# ProPrj_40HZ-AMSAD_2024-06-22.net
KiCad netlist of a schematic drawn in EasyEDA Pro
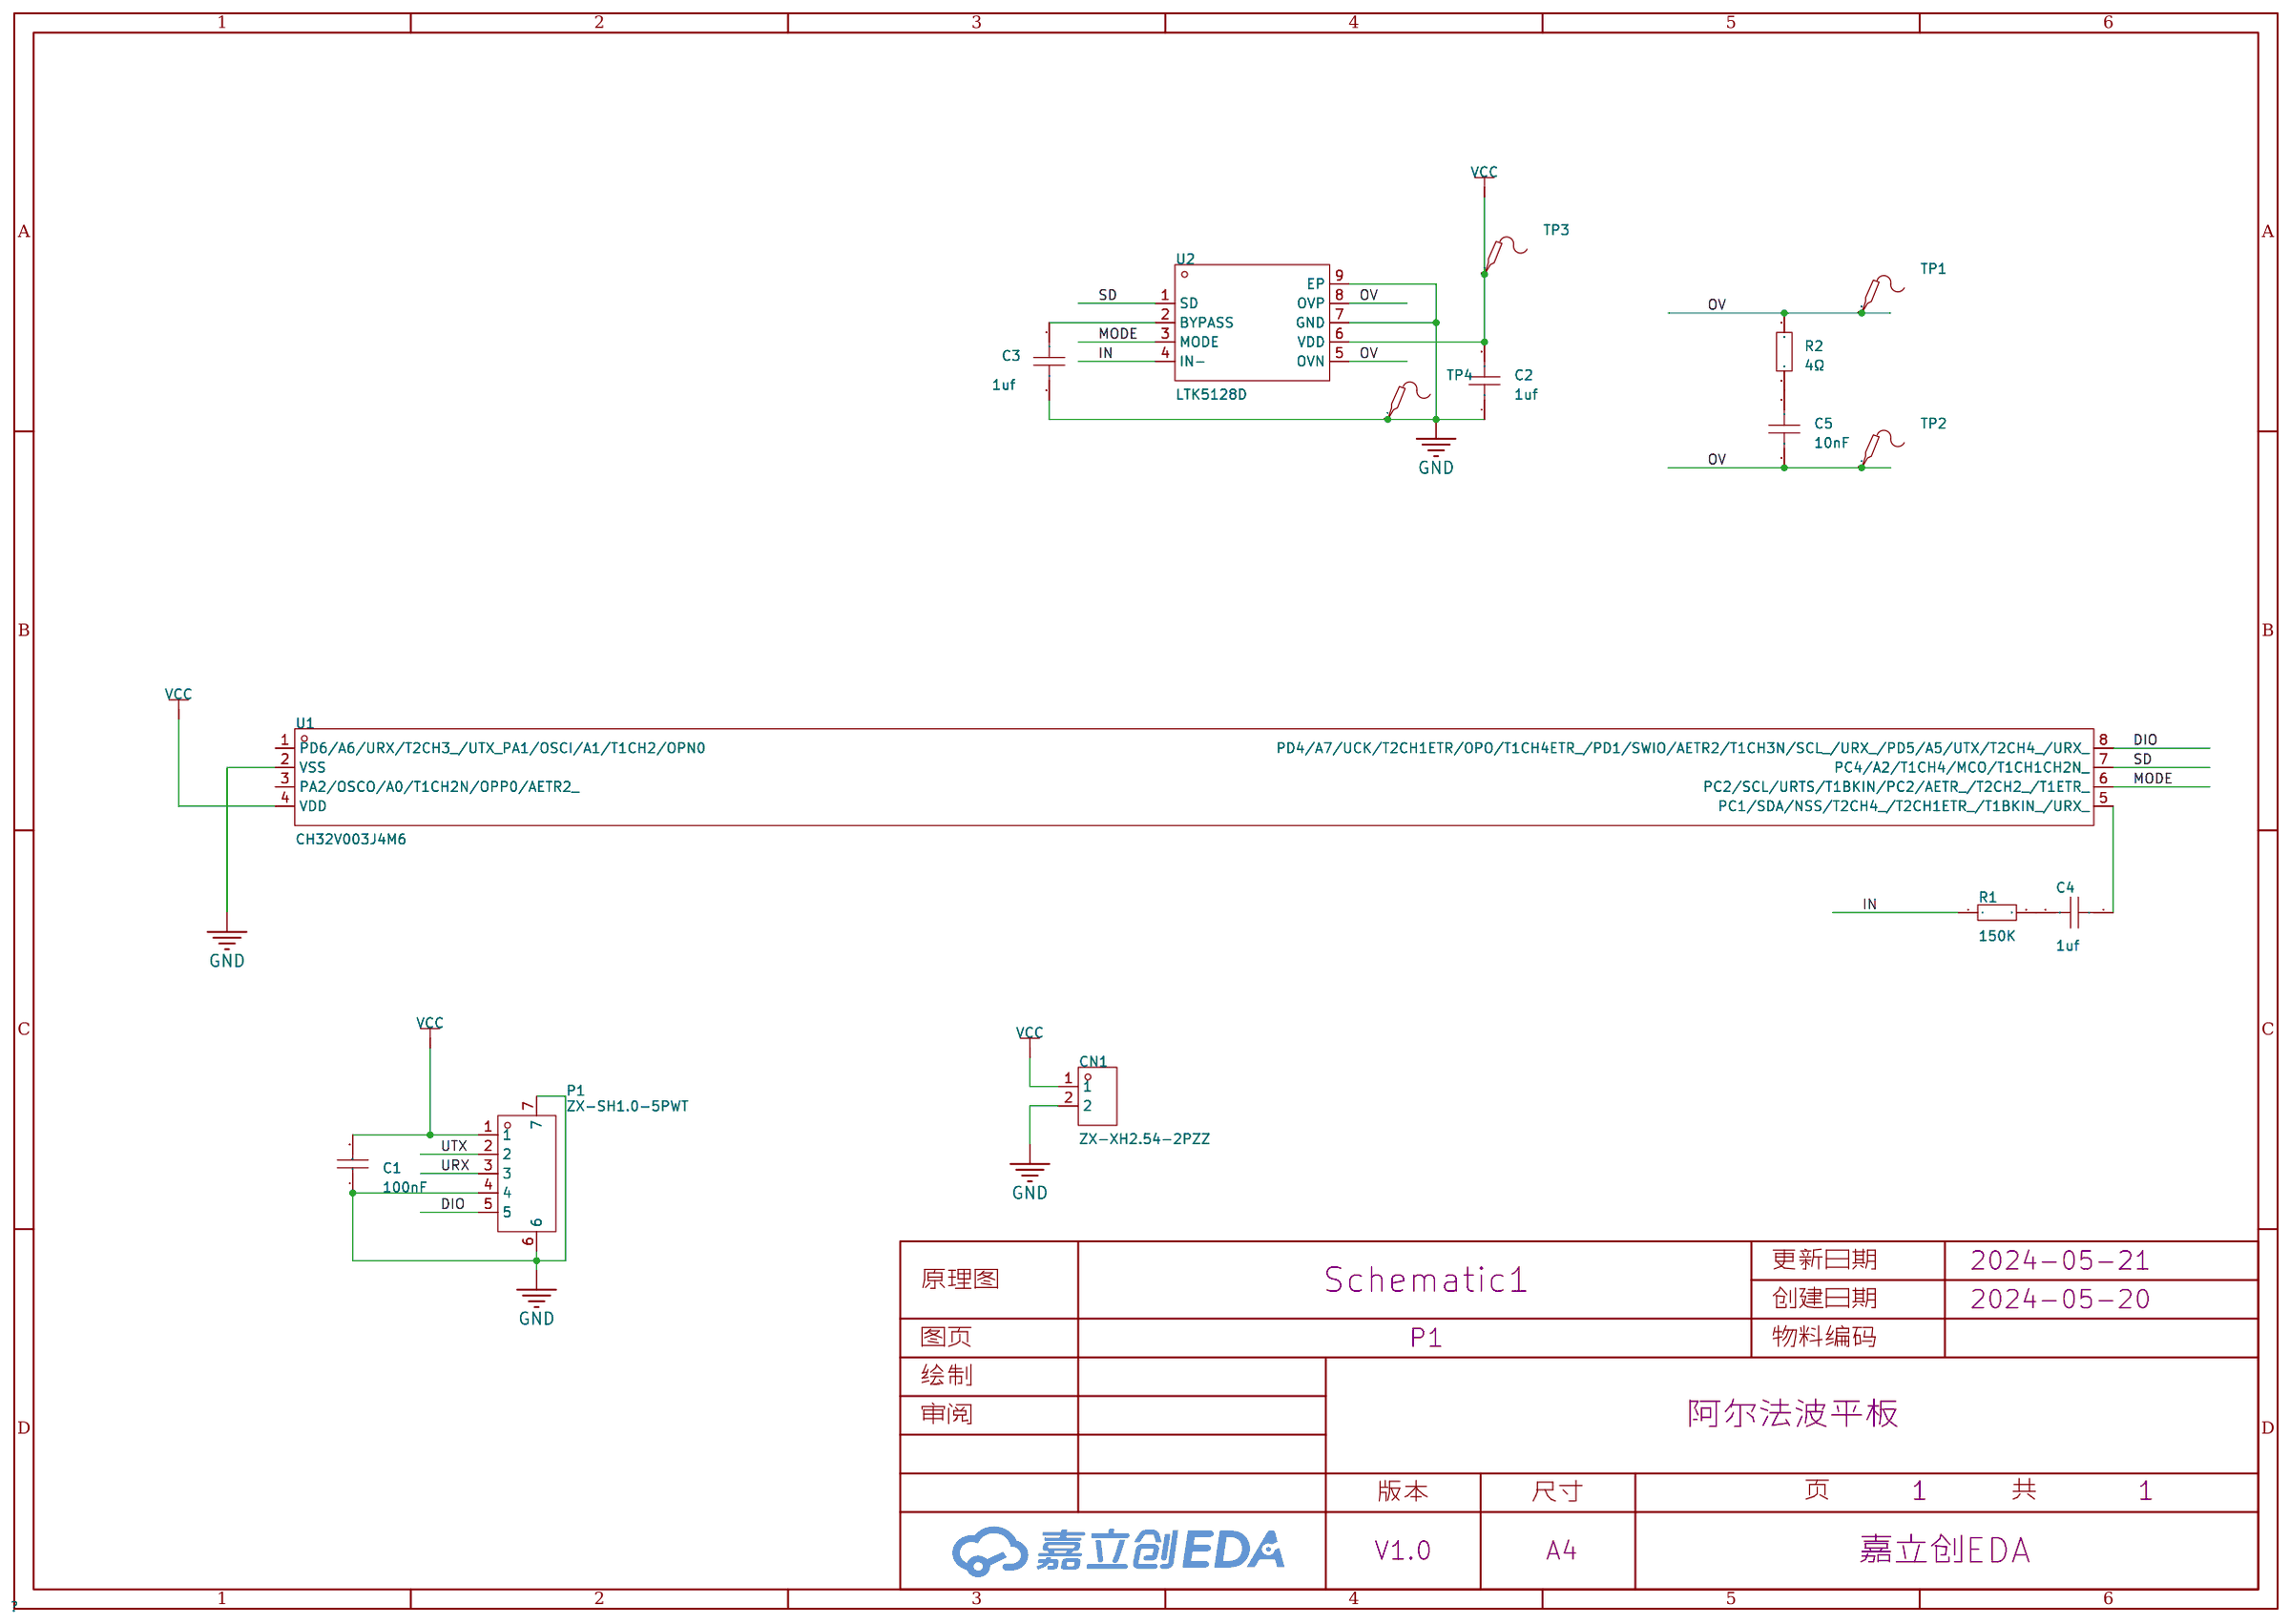
[diagram p0: schematic sheet]

(export (version "E")
  (design (tool "Eeschema 10.0.6"))
  (components
    (comp (ref "C1")
      (value "100nF")
      (footprint "easyedapro:C0603")
      (description "容值:100nF;精度:±10%;额定电压:50V;材质(温度系数):X7R;")
      (fields (field (name "Manufacturer Part") "0603B104K500NT") (field (name "Manufacturer") "FH(风华)"))
      (libsource (lib "easyedapro") (part "0603B104K500NT"))
    )
    (comp (ref "C2")
      (value "1uf")
      (footprint "easyedapro:C0603")
      (libsource (lib "easyedapro") (part "CapAcitance"))
    )
    (comp (ref "C3")
      (value "1uf")
      (footprint "easyedapro:C0603")
      (libsource (lib "easyedapro") (part "CapAcitance"))
    )
    (comp (ref "C4")
      (value "1uf")
      (footprint "easyedapro:C0603")
      (libsource (lib "easyedapro") (part "CapAcitance"))
    )
    (comp (ref "C5")
      (value "10nF")
      (footprint "easyedapro:C0603")
      (libsource (lib "easyedapro") (part "CapAcitance"))
    )
    (comp (ref "CN1")
      (value "ZX-XH2.54-2PZZ")
      (footprint "easyedapro:CONN-TH_2P-P2.50_HX25003-2A")
      (fields (field (name "Manufacturer") "Megastar(兆星)"))
      (libsource (lib "easyedapro") (part "ZX-XH2.54-2PZZ"))
    )
    (comp (ref "P1")
      (value "ZX-SH1.0-5PWT")
      (footprint "easyedapro:CONN-SMD_5P-P1.00_MEGASTAR_ZX-SH1.0-5PWT")
      (fields (field (name "Manufacturer") "Megastar(兆星)"))
      (libsource (lib "easyedapro") (part "ZX-SH1.0-5PWT"))
    )
    (comp (ref "R1") (value "150K") (footprint "easyedapro:R0603") (libsource (lib "easyedapro") (part "电阻")))
    (comp (ref "R2") (value "4Ω") (footprint "easyedapro:R0603") (libsource (lib "easyedapro") (part "电阻")))
    (comp (ref "TP1")
      (value "~")
      (footprint "easyedapro:Test-Point-0.5mm")
      (description "Test Point 测试点")
      (libsource (lib "easyedapro") (part "Test-Point"))
    )
    (comp (ref "TP2")
      (value "~")
      (footprint "easyedapro:Test-Point-0.5mm")
      (description "Test Point 测试点")
      (libsource (lib "easyedapro") (part "Test-Point"))
    )
    (comp (ref "TP3")
      (value "~")
      (footprint "easyedapro:Test-Point-0.5mm")
      (description "Test Point 测试点")
      (libsource (lib "easyedapro") (part "Test-Point"))
    )
    (comp (ref "TP4")
      (value "~")
      (footprint "easyedapro:Test-Point-0.5mm")
      (description "Test Point 测试点")
      (libsource (lib "easyedapro") (part "Test-Point"))
    )
    (comp (ref "U1")
      (value "CH32V003J4M6")
      (footprint "easyedapro:SOP-8_L4.9-W3.8-P1.27-LS6.0-BL")
      (fields (field (name "Manufacturer") "WCH(南京沁恒)"))
      (libsource (lib "easyedapro") (part "CH32V003J4M6_C5346354"))
    )
    (comp (ref "U2")
      (value "LTK5128D")
      (footprint "easyedapro:ESOP-8_L4.9-W3.9-P1.27-LS6.0-BL-EP")
      (description "功放类型:-;输出功率:-;")
      (fields (field (name "Manufacturer") "LTKCHIP(联辉科)"))
      (libsource (lib "easyedapro") (part "LTK5128D"))
    )
  )
  (nets
    (net (code "1") (name "/DIO") (class "Default")
      (node (ref "P1") (pin "5") (pinfunction "5_5") (pintype "unspecified"))
      (node (ref "U1") (pin "8") (pinfunction "PD4/A7/UCK/T2CH1ETR/OPO/T1CH4ETR_/PD1/SWIO/AETR2/T1CH3N/SCL_/URX_/PD5/A5/UTX/T2CH4_/URX__8") (pintype "unspecified"))
    )
    (net (code "2") (name "/IN") (class "Default")
      (node (ref "R1") (pin "1") (pinfunction "1_1") (pintype "input"))
      (node (ref "U2") (pin "4") (pinfunction "IN-_4") (pintype "unspecified"))
    )
    (net (code "3") (name "/MODE") (class "Default")
      (node (ref "U1") (pin "6") (pinfunction "PC2/SCL/URTS/T1BKIN/PC2/AETR_/T2CH2_/T1ETR__6") (pintype "unspecified"))
      (node (ref "U2") (pin "3") (pinfunction "MODE_3") (pintype "unspecified"))
    )
    (net (code "4") (name "/OV") (class "Default")
      (node (ref "C5") (pin "1") (pinfunction "1_1") (pintype "input"))
      (node (ref "R2") (pin "2") (pinfunction "2_2") (pintype "input"))
      (node (ref "TP1") (pin "1") (pinfunction "1_1") (pintype "input"))
      (node (ref "TP2") (pin "1") (pinfunction "1_1") (pintype "input"))
      (node (ref "U2") (pin "5") (pinfunction "OVN_5") (pintype "unspecified"))
      (node (ref "U2") (pin "8") (pinfunction "OVP_8") (pintype "unspecified"))
    )
    (net (code "5") (name "/SD") (class "Default")
      (node (ref "U1") (pin "7") (pinfunction "PC4/A2/T1CH4/MCO/T1CH1CH2N__7") (pintype "unspecified"))
      (node (ref "U2") (pin "1") (pinfunction "SD_1") (pintype "unspecified"))
    )
    (net (code "6") (name "/URX") (class "Default")
      (node (ref "P1") (pin "3") (pinfunction "3_3") (pintype "unspecified"))
    )
    (net (code "7") (name "/UTX") (class "Default")
      (node (ref "P1") (pin "2") (pinfunction "2_2") (pintype "unspecified"))
    )
    (net (code "8") (name "GND") (class "Default")
      (node (ref "C1") (pin "1") (pinfunction "1_1") (pintype "input"))
      (node (ref "C2") (pin "1") (pinfunction "1_1") (pintype "input"))
      (node (ref "C3") (pin "1") (pinfunction "1_1") (pintype "input"))
      (node (ref "CN1") (pin "2") (pinfunction "2_2") (pintype "unspecified"))
      (node (ref "P1") (pin "4") (pinfunction "4_4") (pintype "unspecified"))
      (node (ref "P1") (pin "6") (pinfunction "6_6") (pintype "unspecified"))
      (node (ref "P1") (pin "7") (pinfunction "7_7") (pintype "unspecified"))
      (node (ref "TP4") (pin "1") (pinfunction "1_1") (pintype "input"))
      (node (ref "U1") (pin "2") (pinfunction "VSS_2") (pintype "unspecified"))
      (node (ref "U2") (pin "7") (pinfunction "GND_7") (pintype "unspecified"))
      (node (ref "U2") (pin "9") (pinfunction "EP_9") (pintype "unspecified"))
    )
    (net (code "9") (name "Net-(C4-Pad2)") (class "Default")
      (node (ref "C4") (pin "2") (pinfunction "2_2") (pintype "input"))
      (node (ref "R1") (pin "2") (pinfunction "2_2") (pintype "input"))
    )
    (net (code "10") (name "Net-(C5-Pad2)") (class "Default")
      (node (ref "C5") (pin "2") (pinfunction "2_2") (pintype "input"))
      (node (ref "R2") (pin "1") (pinfunction "1_1") (pintype "input"))
    )
    (net (code "11") (name "Net-(U1-PC1{slash}SDA{slash}NSS{slash}T2CH4_{slash}T2CH1ETR_{slash}T1BKIN_{slash}URX_)") (class "Default")
      (node (ref "C4") (pin "1") (pinfunction "1_1") (pintype "input"))
      (node (ref "U1") (pin "5") (pinfunction "PC1/SDA/NSS/T2CH4_/T2CH1ETR_/T1BKIN_/URX__5") (pintype "unspecified"))
    )
    (net (code "12") (name "Net-(U2-BYPASS)") (class "Default")
      (node (ref "C3") (pin "2") (pinfunction "2_2") (pintype "input"))
      (node (ref "U2") (pin "2") (pinfunction "BYPASS_2") (pintype "unspecified"))
    )
    (net (code "13") (name "VCC") (class "Default")
      (node (ref "C1") (pin "2") (pinfunction "2_2") (pintype "input"))
      (node (ref "C2") (pin "2") (pinfunction "2_2") (pintype "input"))
      (node (ref "CN1") (pin "1") (pinfunction "1_1") (pintype "unspecified"))
      (node (ref "P1") (pin "1") (pinfunction "1_1") (pintype "unspecified"))
      (node (ref "TP3") (pin "1") (pinfunction "1_1") (pintype "input"))
      (node (ref "U1") (pin "4") (pinfunction "VDD_4") (pintype "unspecified"))
      (node (ref "U2") (pin "6") (pinfunction "VDD_6") (pintype "unspecified"))
    )
    (net (code "14") (name "unconnected-(U1-PA2{slash}OSCO{slash}A0{slash}T1CH2N{slash}OPP0{slash}AETR2_-Pad3)") (class "Default")
      (node (ref "U1") (pin "3") (pinfunction "PA2/OSCO/A0/T1CH2N/OPP0/AETR2__3") (pintype "unspecified"))
    )
    (net (code "15") (name "unconnected-(U1-PD6{slash}A6{slash}URX{slash}T2CH3_{slash}UTX_PA1{slash}OSCI{slash}A1{slash}T1CH2{slash}OPN0-Pad1)") (class "Default")
      (node (ref "U1") (pin "1") (pinfunction "PD6/A6/URX/T2CH3_/UTX_PA1/OSCI/A1/T1CH2/OPN0_1") (pintype "unspecified"))
    )
  )
)
